# Adafruit_Feather_M0_RFMxx.net
KiCad netlist of a schematic drawn in EAGLE
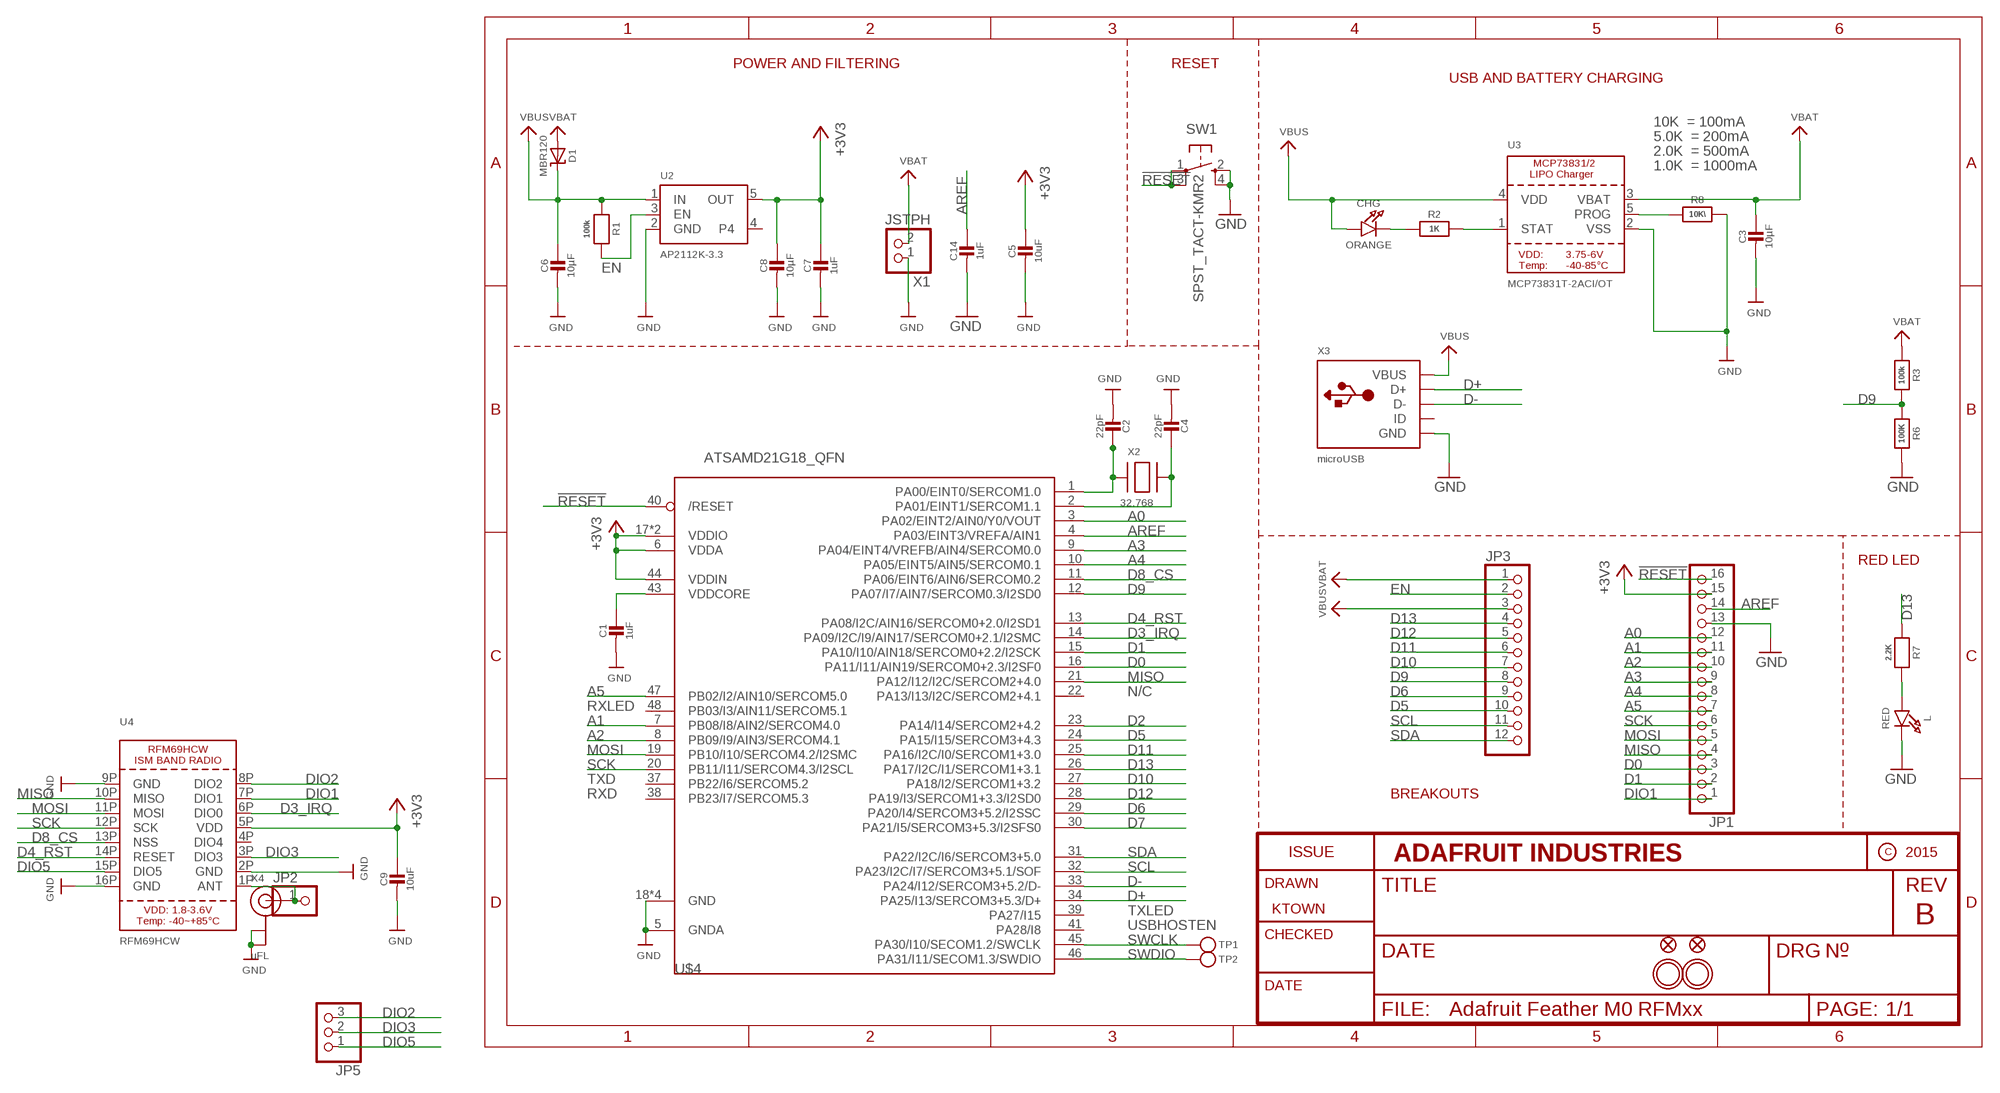
[diagram p0: schematic, sheet 1]

(export (version "E")
  (design (tool "Eeschema 10.0.6"))
  (components
    (comp (ref "C1")
      (value "1uF")
      (footprint "eagle-import:0603-NO")
      (libsource (lib "eagle-import") (part "CAP_CERAMIC0603_NO"))
    )
    (comp (ref "C2")
      (value "22pF")
      (footprint "eagle-import:0603-NO")
      (libsource (lib "eagle-import") (part "CAP_CERAMIC0603_NO"))
    )
    (comp (ref "C3")
      (value "10µF")
      (footprint "eagle-import:0805-NO")
      (libsource (lib "eagle-import") (part "CAP_CERAMIC0805-NOOUTLINE"))
    )
    (comp (ref "C4")
      (value "22pF")
      (footprint "eagle-import:0603-NO")
      (libsource (lib "eagle-import") (part "CAP_CERAMIC0603_NO"))
    )
    (comp (ref "C5")
      (value "10uF")
      (footprint "eagle-import:0805-NO")
      (libsource (lib "eagle-import") (part "CAP_CERAMIC0805-NOOUTLINE"))
    )
    (comp (ref "C6")
      (value "10µF")
      (footprint "eagle-import:0805-NO")
      (libsource (lib "eagle-import") (part "CAP_CERAMIC0805-NOOUTLINE"))
    )
    (comp (ref "C7")
      (value "1uF")
      (footprint "eagle-import:0603-NO")
      (libsource (lib "eagle-import") (part "CAP_CERAMIC0603_NO"))
    )
    (comp (ref "C8")
      (value "10µF")
      (footprint "eagle-import:0805-NO")
      (libsource (lib "eagle-import") (part "CAP_CERAMIC0805-NOOUTLINE"))
    )
    (comp (ref "C9")
      (value "10uF")
      (footprint "eagle-import:0805-NO")
      (libsource (lib "eagle-import") (part "CAP_CERAMIC0805-NOOUTLINE"))
    )
    (comp (ref "C14")
      (value "1uF")
      (footprint "eagle-import:0603-NO")
      (libsource (lib "eagle-import") (part "CAP_CERAMIC0603_NO"))
    )
    (comp (ref "CHG")
      (value "ORANGE")
      (footprint "eagle-import:CHIPLED_0805_NOOUTLINE")
      (libsource (lib "eagle-import") (part "LED0805_NOOUTLINE"))
    )
    (comp (ref "D1")
      (value "MBR120")
      (footprint "eagle-import:SOD-123")
      (libsource (lib "eagle-import") (part "DIODE-SCHOTTKYSOD-123"))
    )
    (comp (ref "JP1")
      (value "HEADER-1X16ROUND")
      (footprint "eagle-import:1X16_ROUND")
      (libsource (lib "eagle-import") (part "HEADER-1X16ROUND"))
    )
    (comp (ref "JP2")
      (value "HEADER-1X1ROUND")
      (footprint "eagle-import:1X01_ROUND")
      (libsource (lib "eagle-import") (part "HEADER-1X1ROUND"))
    )
    (comp (ref "JP3")
      (value "HEADER-1X12")
      (footprint "eagle-import:1X12_ROUND")
      (libsource (lib "eagle-import") (part "HEADER-1X12"))
    )
    (comp (ref "JP5")
      (value "HEADER-1X3ROUND")
      (footprint "eagle-import:1X03_ROUND")
      (libsource (lib "eagle-import") (part "HEADER-1X3ROUND"))
    )
    (comp (ref "L")
      (value "RED")
      (footprint "eagle-import:CHIPLED_0805_NOOUTLINE")
      (libsource (lib "eagle-import") (part "LED0805_NOOUTLINE"))
    )
    (comp (ref "R1")
      (value "100k")
      (footprint "eagle-import:0603-NO")
      (libsource (lib "eagle-import") (part "RESISTOR_0603_NOOUT"))
    )
    (comp (ref "R2")
      (value "1K")
      (footprint "eagle-import:0603-NO")
      (libsource (lib "eagle-import") (part "RESISTOR_0603_NOOUT"))
    )
    (comp (ref "R3")
      (value "100k")
      (footprint "eagle-import:0603-NO")
      (libsource (lib "eagle-import") (part "RESISTOR_0603_NOOUT"))
    )
    (comp (ref "R6")
      (value "100K")
      (footprint "eagle-import:0603-NO")
      (libsource (lib "eagle-import") (part "RESISTOR_0603_NOOUT"))
    )
    (comp (ref "R7")
      (value "2.2K")
      (footprint "eagle-import:0603-NO")
      (libsource (lib "eagle-import") (part "RESISTOR_0603_NOOUT"))
    )
    (comp (ref "R8")
      (value "10K\\")
      (footprint "eagle-import:0603-NO")
      (libsource (lib "eagle-import") (part "RESISTOR_0603_NOOUT"))
    )
    (comp (ref "SW1")
      (value "SPST_TACT-KMR2")
      (footprint "eagle-import:KMR2")
      (libsource (lib "eagle-import") (part "SPST_TACT-KMR2"))
    )
    (comp (ref "TP1")
      (value "TESTPOINTROUND1.5MM")
      (footprint "eagle-import:TESTPOINT_ROUND_1.5MM")
      (libsource (lib "eagle-import") (part "TESTPOINTROUND1.5MM"))
    )
    (comp (ref "TP2")
      (value "TESTPOINTROUND1.5MM")
      (footprint "eagle-import:TESTPOINT_ROUND_1.5MM")
      (libsource (lib "eagle-import") (part "TESTPOINTROUND1.5MM"))
    )
    (comp (ref "U$4")
      (value "ATSAMD21G18_QFN")
      (footprint "eagle-import:TQFN48_7MM")
      (libsource (lib "eagle-import") (part "ATSAMD21J_QFN"))
    )
    (comp (ref "U$31")
      (value "MOUNTINGHOLE2.5")
      (footprint "eagle-import:MOUNTINGHOLE_2.5_PLATED")
      (libsource (lib "eagle-import") (part "MOUNTINGHOLE2.5"))
    )
    (comp (ref "U$32")
      (value "MOUNTINGHOLE2.5")
      (footprint "eagle-import:MOUNTINGHOLE_2.5_PLATED")
      (libsource (lib "eagle-import") (part "MOUNTINGHOLE2.5"))
    )
    (comp (ref "U$34")
      (value "FIDUCIAL\"\"")
      (footprint "eagle-import:FIDUCIAL_1MM")
      (libsource (lib "eagle-import") (part "FIDUCIAL{dblquote}{dblquote}"))
    )
    (comp (ref "U$35")
      (value "FIDUCIAL\"\"")
      (footprint "eagle-import:FIDUCIAL_1MM")
      (libsource (lib "eagle-import") (part "FIDUCIAL{dblquote}{dblquote}"))
    )
    (comp (ref "U2")
      (value "AP2112K-3.3")
      (footprint "eagle-import:SOT23-5")
      (libsource (lib "eagle-import") (part "VREG_SOT23-5"))
    )
    (comp (ref "U3")
      (value "MCP73831T-2ACI/OT")
      (footprint "eagle-import:SOT23-5")
      (libsource (lib "eagle-import") (part "MCP73831/2"))
    )
    (comp (ref "U4")
      (value "RFM69HCW")
      (footprint "eagle-import:RFMHCW_SMT")
      (libsource (lib "eagle-import") (part "RFM69HCW_SMT"))
    )
    (comp (ref "X1")
      (value "JSTPH")
      (footprint "eagle-import:JSTPH2")
      (libsource (lib "eagle-import") (part "CON_JST_PH_2PIN"))
    )
    (comp (ref "X2")
      (value "32.768")
      (footprint "eagle-import:XTAL3215")
      (libsource (lib "eagle-import") (part "XTAL-3.2X1.5"))
    )
    (comp (ref "X3")
      (value "microUSB")
      (footprint "eagle-import:4UCONN_20329_V2")
      (libsource (lib "eagle-import") (part "USB_MICRO_20329_V2"))
    )
    (comp (ref "X4")
      (value "uFL")
      (footprint "eagle-import:U.FL")
      (libsource (lib "eagle-import") (part "ANTENNA_U.FL"))
    )
  )
  (nets
    (net (code "1") (name "+3V3") (class "Default")
      (node (ref "C5") (pin "1") (pinfunction "1_1") (pintype "passive"))
      (node (ref "C7") (pin "1") (pinfunction "1_1") (pintype "passive"))
      (node (ref "C8") (pin "1") (pinfunction "1_1") (pintype "passive"))
      (node (ref "C9") (pin "1") (pinfunction "1_1") (pintype "passive"))
      (node (ref "JP1") (pin "15") (pinfunction "15_15") (pintype "passive"))
      (node (ref "U$4") (pin "17") (pinfunction "VDDIO_17") (pintype "power_in"))
      (node (ref "U$4") (pin "36") (pinfunction "VDDIO_36") (pintype "power_in"))
      (node (ref "U$4") (pin "44") (pinfunction "VDDIN_44") (pintype "power_in"))
      (node (ref "U$4") (pin "6") (pinfunction "VDDA_6") (pintype "power_in"))
      (node (ref "U2") (pin "5") (pinfunction "OUT_5") (pintype "power_in"))
      (node (ref "U4") (pin "5P") (pinfunction "VDD_5P") (pintype "power_in"))
    )
    (net (code "2") (name "/A0") (class "Default")
      (node (ref "JP1") (pin "12") (pinfunction "12_12") (pintype "passive"))
      (node (ref "U$4") (pin "3") (pinfunction "PA02/EINT2/AIN0/Y0/VOUT_3") (pintype "bidirectional"))
    )
    (net (code "3") (name "/A1") (class "Default")
      (node (ref "JP1") (pin "11") (pinfunction "11_11") (pintype "passive"))
      (node (ref "U$4") (pin "7") (pinfunction "PB08/I8/AIN2/SERCOM4.0_7") (pintype "bidirectional"))
    )
    (net (code "4") (name "/A2") (class "Default")
      (node (ref "JP1") (pin "10") (pinfunction "10_10") (pintype "passive"))
      (node (ref "U$4") (pin "8") (pinfunction "PB09/I9/AIN3/SERCOM4.1_8") (pintype "bidirectional"))
    )
    (net (code "5") (name "/A3") (class "Default")
      (node (ref "JP1") (pin "9") (pinfunction "9_9") (pintype "passive"))
      (node (ref "U$4") (pin "9") (pinfunction "PA04/EINT4/VREFB/AIN4/SERCOM0.0_9") (pintype "bidirectional"))
    )
    (net (code "6") (name "/A4") (class "Default")
      (node (ref "JP1") (pin "8") (pinfunction "8_8") (pintype "passive"))
      (node (ref "U$4") (pin "10") (pinfunction "PA05/EINT5/AIN5/SERCOM0.1_10") (pintype "bidirectional"))
    )
    (net (code "7") (name "/A5") (class "Default")
      (node (ref "JP1") (pin "7") (pinfunction "7_7") (pintype "passive"))
      (node (ref "U$4") (pin "47") (pinfunction "PB02/I2/AIN10/SERCOM5.0_47") (pintype "bidirectional"))
    )
    (net (code "8") (name "/AREF") (class "Default")
      (node (ref "C14") (pin "1") (pinfunction "1_1") (pintype "passive"))
      (node (ref "JP1") (pin "14") (pinfunction "14_14") (pintype "passive"))
      (node (ref "U$4") (pin "4") (pinfunction "PA03/EINT3/VREFA/AIN1_4") (pintype "bidirectional"))
    )
    (net (code "9") (name "/D+") (class "Default")
      (node (ref "U$4") (pin "34") (pinfunction "PA25/I13/SERCOM3+5.3/D+_34") (pintype "bidirectional"))
      (node (ref "X3") (pin "D+") (pinfunction "D+_D+") (pintype "bidirectional"))
    )
    (net (code "10") (name "/D-") (class "Default")
      (node (ref "U$4") (pin "33") (pinfunction "PA24/I12/SERCOM3+5.2/D-_33") (pintype "bidirectional"))
      (node (ref "X3") (pin "D-") (pinfunction "D-_D-") (pintype "bidirectional"))
    )
    (net (code "11") (name "/D0") (class "Default")
      (node (ref "JP1") (pin "3") (pinfunction "3_3") (pintype "passive"))
      (node (ref "U$4") (pin "16") (pinfunction "PA11/I11/AIN19/SERCOM0+2.3/I2SF0_16") (pintype "bidirectional"))
    )
    (net (code "12") (name "/D1") (class "Default")
      (node (ref "JP1") (pin "2") (pinfunction "2_2") (pintype "passive"))
      (node (ref "U$4") (pin "15") (pinfunction "PA10/I10/AIN18/SERCOM0+2.2/I2SCK_15") (pintype "bidirectional"))
    )
    (net (code "13") (name "/D2") (class "Default")
      (node (ref "U$4") (pin "23") (pinfunction "PA14/I14/SERCOM2+4.2_23") (pintype "bidirectional"))
    )
    (net (code "14") (name "/D3_IRQ") (class "Default")
      (node (ref "U$4") (pin "14") (pinfunction "PA09/I2C/I9/AIN17/SERCOM0+2.1/I2SMC_14") (pintype "bidirectional"))
      (node (ref "U4") (pin "6P") (pinfunction "DIO0_6P") (pintype "bidirectional"))
    )
    (net (code "15") (name "/D4_RST") (class "Default")
      (node (ref "U$4") (pin "13") (pinfunction "PA08/I2C/AIN16/SERCOM0+2.0/I2SD1_13") (pintype "bidirectional"))
      (node (ref "U4") (pin "14P") (pinfunction "RESET_14P") (pintype "input"))
    )
    (net (code "16") (name "/D5") (class "Default")
      (node (ref "JP3") (pin "10") (pinfunction "10_10") (pintype "passive"))
      (node (ref "U$4") (pin "24") (pinfunction "PA15/I15/SERCOM3+4.3_24") (pintype "bidirectional"))
    )
    (net (code "17") (name "/D6") (class "Default")
      (node (ref "JP3") (pin "9") (pinfunction "9_9") (pintype "passive"))
      (node (ref "U$4") (pin "29") (pinfunction "PA20/I4/SERCOM3+5.2/I2SSC_29") (pintype "bidirectional"))
    )
    (net (code "18") (name "/D7") (class "Default")
      (node (ref "U$4") (pin "30") (pinfunction "PA21/I5/SERCOM3+5.3/I2SFS0_30") (pintype "bidirectional"))
    )
    (net (code "19") (name "/D8_CS") (class "Default")
      (node (ref "U$4") (pin "11") (pinfunction "PA06/EINT6/AIN6/SERCOM0.2_11") (pintype "bidirectional"))
      (node (ref "U4") (pin "13P") (pinfunction "NSS_13P") (pintype "input"))
    )
    (net (code "20") (name "/D9") (class "Default")
      (node (ref "JP3") (pin "8") (pinfunction "8_8") (pintype "passive"))
      (node (ref "R3") (pin "2") (pinfunction "2_2") (pintype "passive"))
      (node (ref "R6") (pin "1") (pinfunction "1_1") (pintype "passive"))
      (node (ref "U$4") (pin "12") (pinfunction "PA07/I7/AIN7/SERCOM0.3/I2SD0_12") (pintype "bidirectional"))
    )
    (net (code "21") (name "/D10") (class "Default")
      (node (ref "JP3") (pin "7") (pinfunction "7_7") (pintype "passive"))
      (node (ref "U$4") (pin "27") (pinfunction "PA18/I2/SERCOM1+3.2_27") (pintype "bidirectional"))
    )
    (net (code "22") (name "/D11") (class "Default")
      (node (ref "JP3") (pin "6") (pinfunction "6_6") (pintype "passive"))
      (node (ref "U$4") (pin "25") (pinfunction "PA16/I2C/I0/SERCOM1+3.0_25") (pintype "bidirectional"))
    )
    (net (code "23") (name "/D12") (class "Default")
      (node (ref "JP3") (pin "5") (pinfunction "5_5") (pintype "passive"))
      (node (ref "U$4") (pin "28") (pinfunction "PA19/I3/SERCOM1+3.3/I2SD0_28") (pintype "bidirectional"))
    )
    (net (code "24") (name "/D13") (class "Default")
      (node (ref "JP3") (pin "4") (pinfunction "4_4") (pintype "passive"))
      (node (ref "R7") (pin "1") (pinfunction "1_1") (pintype "passive"))
      (node (ref "U$4") (pin "26") (pinfunction "PA17/I2C/I1/SERCOM1+3.1_26") (pintype "bidirectional"))
    )
    (net (code "25") (name "/DIO1") (class "Default")
      (node (ref "JP1") (pin "1") (pinfunction "1_1") (pintype "passive"))
      (node (ref "U4") (pin "7P") (pinfunction "DIO1_7P") (pintype "bidirectional"))
    )
    (net (code "26") (name "/DIO2") (class "Default")
      (node (ref "JP5") (pin "3") (pinfunction "3_3") (pintype "passive"))
      (node (ref "U4") (pin "8P") (pinfunction "DIO2_8P") (pintype "bidirectional"))
    )
    (net (code "27") (name "/DIO3") (class "Default")
      (node (ref "JP5") (pin "2") (pinfunction "2_2") (pintype "passive"))
      (node (ref "U4") (pin "3P") (pinfunction "DIO3_3P") (pintype "bidirectional"))
    )
    (net (code "28") (name "/DIO5") (class "Default")
      (node (ref "JP5") (pin "1") (pinfunction "1_1") (pintype "passive"))
      (node (ref "U4") (pin "15P") (pinfunction "DIO5_15P") (pintype "bidirectional"))
    )
    (net (code "29") (name "/EN") (class "Default")
      (node (ref "JP3") (pin "2") (pinfunction "2_2") (pintype "passive"))
      (node (ref "R1") (pin "2") (pinfunction "2_2") (pintype "passive"))
      (node (ref "U2") (pin "3") (pinfunction "EN_3") (pintype "input"))
    )
    (net (code "30") (name "/MISO") (class "Default")
      (node (ref "JP1") (pin "4") (pinfunction "4_4") (pintype "passive"))
      (node (ref "U$4") (pin "21") (pinfunction "PA12/I12/I2C/SERCOM2+4.0_21") (pintype "bidirectional"))
      (node (ref "U4") (pin "10P") (pinfunction "MISO_10P") (pintype "output"))
    )
    (net (code "31") (name "/MOSI") (class "Default")
      (node (ref "JP1") (pin "5") (pinfunction "5_5") (pintype "passive"))
      (node (ref "U$4") (pin "19") (pinfunction "PB10/I10/SERCOM4.2/I2SMC_19") (pintype "bidirectional"))
      (node (ref "U4") (pin "11P") (pinfunction "MOSI_11P") (pintype "input"))
    )
    (net (code "32") (name "/SCK") (class "Default")
      (node (ref "JP1") (pin "6") (pinfunction "6_6") (pintype "passive"))
      (node (ref "U$4") (pin "20") (pinfunction "PB11/I11/SERCOM4.3/I2SCL_20") (pintype "bidirectional"))
      (node (ref "U4") (pin "12P") (pinfunction "SCK_12P") (pintype "input"))
    )
    (net (code "33") (name "/SCL") (class "Default")
      (node (ref "JP3") (pin "11") (pinfunction "11_11") (pintype "passive"))
      (node (ref "U$4") (pin "32") (pinfunction "PA23/I2C/I7/SERCOM3+5.1/SOF_32") (pintype "bidirectional"))
    )
    (net (code "34") (name "/SDA") (class "Default")
      (node (ref "JP3") (pin "12") (pinfunction "12_12") (pintype "passive"))
      (node (ref "U$4") (pin "31") (pinfunction "PA22/I2C/I6/SERCOM3+5.0_31") (pintype "bidirectional"))
    )
    (net (code "35") (name "/SWCLK") (class "Default")
      (node (ref "TP1") (pin "P$1") (pinfunction "P$1_P$1") (pintype "bidirectional"))
      (node (ref "U$4") (pin "45") (pinfunction "PA30/I10/SECOM1.2/SWCLK_45") (pintype "bidirectional"))
    )
    (net (code "36") (name "/SWDIO") (class "Default")
      (node (ref "TP2") (pin "P$1") (pinfunction "P$1_P$1") (pintype "bidirectional"))
      (node (ref "U$4") (pin "46") (pinfunction "PA31/I11/SECOM1.3/SWDIO_46") (pintype "bidirectional"))
    )
    (net (code "37") (name "/~{RESET}") (class "Default")
      (node (ref "JP1") (pin "16") (pinfunction "16_16") (pintype "passive"))
      (node (ref "SW1") (pin "1") (pinfunction "P_1") (pintype "passive"))
      (node (ref "SW1") (pin "3") (pinfunction "P1_3") (pintype "passive"))
      (node (ref "U$4") (pin "40") (pinfunction "/RESET_40") (pintype "bidirectional"))
    )
    (net (code "38") (name "GND") (class "Default")
      (node (ref "C1") (pin "2") (pinfunction "2_2") (pintype "passive"))
      (node (ref "C14") (pin "2") (pinfunction "2_2") (pintype "passive"))
      (node (ref "C2") (pin "2") (pinfunction "2_2") (pintype "passive"))
      (node (ref "C3") (pin "2") (pinfunction "2_2") (pintype "passive"))
      (node (ref "C4") (pin "2") (pinfunction "2_2") (pintype "passive"))
      (node (ref "C5") (pin "2") (pinfunction "2_2") (pintype "passive"))
      (node (ref "C6") (pin "2") (pinfunction "2_2") (pintype "passive"))
      (node (ref "C7") (pin "2") (pinfunction "2_2") (pintype "passive"))
      (node (ref "C8") (pin "2") (pinfunction "2_2") (pintype "passive"))
      (node (ref "C9") (pin "2") (pinfunction "2_2") (pintype "passive"))
      (node (ref "JP1") (pin "13") (pinfunction "13_13") (pintype "passive"))
      (node (ref "L") (pin "C") (pinfunction "C_C") (pintype "passive"))
      (node (ref "R6") (pin "2") (pinfunction "2_2") (pintype "passive"))
      (node (ref "R8") (pin "2") (pinfunction "2_2") (pintype "passive"))
      (node (ref "SW1") (pin "2") (pinfunction "S_2") (pintype "passive"))
      (node (ref "SW1") (pin "4") (pinfunction "S1_4") (pintype "passive"))
      (node (ref "U$4") (pin "18") (pinfunction "GND_18") (pintype "power_in"))
      (node (ref "U$4") (pin "35") (pinfunction "GND_35") (pintype "power_in"))
      (node (ref "U$4") (pin "42") (pinfunction "GND_42") (pintype "power_in"))
      (node (ref "U$4") (pin "5") (pinfunction "GNDA_5") (pintype "power_in"))
      (node (ref "U$4") (pin "THERMAL") (pinfunction "GND_THERMAL") (pintype "power_in"))
      (node (ref "U2") (pin "2") (pinfunction "GND_2") (pintype "power_in"))
      (node (ref "U3") (pin "2") (pinfunction "VSS_2") (pintype "power_in"))
      (node (ref "U4") (pin "16P") (pinfunction "GND_16P") (pintype "power_in"))
      (node (ref "U4") (pin "2P") (pinfunction "GND_2P") (pintype "power_in"))
      (node (ref "U4") (pin "9P") (pinfunction "GND_9P") (pintype "power_in"))
      (node (ref "X1") (pin "1") (pinfunction "1_1") (pintype "passive"))
      (node (ref "X3") (pin "BASE@1") (pinfunction "GND_BASE@1") (pintype "power_in"))
      (node (ref "X3") (pin "BASE@2") (pinfunction "GND_BASE@2") (pintype "power_in"))
      (node (ref "X3") (pin "GND") (pinfunction "GND_GND") (pintype "power_in"))
      (node (ref "X3") (pin "SPRT@1") (pinfunction "GND_SPRT@1") (pintype "power_in"))
      (node (ref "X3") (pin "SPRT@2") (pinfunction "GND_SPRT@2") (pintype "power_in"))
      (node (ref "X3") (pin "SPRT@3") (pinfunction "GND_SPRT@3") (pintype "power_in"))
      (node (ref "X3") (pin "SPRT@4") (pinfunction "GND_SPRT@4") (pintype "power_in"))
      (node (ref "X4") (pin "1") (pinfunction "GND_1") (pintype "passive"))
      (node (ref "X4") (pin "2") (pinfunction "GND_2") (pintype "passive"))
    )
    (net (code "39") (name "Net-(CHG-PadC)") (class "Default")
      (node (ref "CHG") (pin "C") (pinfunction "C_C") (pintype "passive"))
      (node (ref "R2") (pin "1") (pinfunction "1_1") (pintype "passive"))
    )
    (net (code "40") (name "Net-(L-PadA)") (class "Default")
      (node (ref "L") (pin "A") (pinfunction "A_A") (pintype "passive"))
      (node (ref "R7") (pin "2") (pinfunction "2_2") (pintype "passive"))
    )
    (net (code "41") (name "Net-(U$4-PA00{slash}EINT0{slash}SERCOM1.0)") (class "Default")
      (node (ref "C2") (pin "1") (pinfunction "1_1") (pintype "passive"))
      (node (ref "U$4") (pin "1") (pinfunction "PA00/EINT0/SERCOM1.0_1") (pintype "bidirectional"))
      (node (ref "X2") (pin "P$1") (pinfunction "P$1_P$1") (pintype "bidirectional"))
    )
    (net (code "42") (name "Net-(U$4-PA01{slash}EINT1{slash}SERCOM1.1)") (class "Default")
      (node (ref "C4") (pin "1") (pinfunction "1_1") (pintype "passive"))
      (node (ref "U$4") (pin "2") (pinfunction "PA01/EINT1/SERCOM1.1_2") (pintype "bidirectional"))
      (node (ref "X2") (pin "P$2") (pinfunction "P$2_P$2") (pintype "bidirectional"))
    )
    (net (code "43") (name "Net-(U$4-VDDCORE)") (class "Default")
      (node (ref "C1") (pin "1") (pinfunction "1_1") (pintype "passive"))
      (node (ref "U$4") (pin "43") (pinfunction "VDDCORE_43") (pintype "power_in"))
    )
    (net (code "44") (name "Net-(U3-PROG)") (class "Default")
      (node (ref "R8") (pin "1") (pinfunction "1_1") (pintype "passive"))
      (node (ref "U3") (pin "5") (pinfunction "PROG_5") (pintype "input"))
    )
    (net (code "45") (name "Net-(U3-STAT)") (class "Default")
      (node (ref "R2") (pin "2") (pinfunction "2_2") (pintype "passive"))
      (node (ref "U3") (pin "1") (pinfunction "STAT_1") (pintype "output"))
    )
    (net (code "46") (name "Net-(U4-ANT)") (class "Default")
      (node (ref "JP2") (pin "1") (pinfunction "1_1") (pintype "passive"))
      (node (ref "U4") (pin "1P") (pinfunction "ANT_1P") (pintype "bidirectional"))
      (node (ref "X4") (pin "3") (pinfunction "SIGNAL_3") (pintype "passive"))
    )
    (net (code "47") (name "VBAT") (class "Default")
      (node (ref "C3") (pin "1") (pinfunction "1_1") (pintype "passive"))
      (node (ref "D1") (pin "A") (pinfunction "A_A") (pintype "passive"))
      (node (ref "JP3") (pin "1") (pinfunction "1_1") (pintype "passive"))
      (node (ref "R3") (pin "1") (pinfunction "1_1") (pintype "passive"))
      (node (ref "U3") (pin "3") (pinfunction "VBAT_3") (pintype "power_in"))
      (node (ref "X1") (pin "2") (pinfunction "2_2") (pintype "passive"))
    )
    (net (code "48") (name "VBUS") (class "Default")
      (node (ref "C6") (pin "1") (pinfunction "1_1") (pintype "passive"))
      (node (ref "CHG") (pin "A") (pinfunction "A_A") (pintype "passive"))
      (node (ref "D1") (pin "C") (pinfunction "C_C") (pintype "passive"))
      (node (ref "JP3") (pin "3") (pinfunction "3_3") (pintype "passive"))
      (node (ref "R1") (pin "1") (pinfunction "1_1") (pintype "passive"))
      (node (ref "U2") (pin "1") (pinfunction "IN_1") (pintype "power_in"))
      (node (ref "U3") (pin "4") (pinfunction "VDD_4") (pintype "power_in"))
      (node (ref "X3") (pin "VBUS") (pinfunction "VBUS_VBUS") (pintype "power_in"))
    )
    (net (code "49") (name "unconnected-(U$4-PA13{slash}I13{slash}I2C{slash}SERCOM2+4.1-Pad22)") (class "Default")
      (node (ref "U$4") (pin "22") (pinfunction "PA13/I13/I2C/SERCOM2+4.1_22") (pintype "bidirectional"))
    )
    (net (code "50") (name "unconnected-(U$4-PA27{slash}I15-Pad39)") (class "Default")
      (node (ref "U$4") (pin "39") (pinfunction "PA27/I15_39") (pintype "bidirectional"))
    )
    (net (code "51") (name "unconnected-(U$4-PA28{slash}I8-Pad41)") (class "Default")
      (node (ref "U$4") (pin "41") (pinfunction "PA28/I8_41") (pintype "bidirectional"))
    )
    (net (code "52") (name "unconnected-(U$4-PB03{slash}I3{slash}AIN11{slash}SERCOM5.1-Pad48)") (class "Default")
      (node (ref "U$4") (pin "48") (pinfunction "PB03/I3/AIN11/SERCOM5.1_48") (pintype "bidirectional"))
    )
    (net (code "53") (name "unconnected-(U$4-PB22{slash}I6{slash}SERCOM5.2-Pad37)") (class "Default")
      (node (ref "U$4") (pin "37") (pinfunction "PB22/I6/SERCOM5.2_37") (pintype "bidirectional"))
    )
    (net (code "54") (name "unconnected-(U$4-PB23{slash}I7{slash}SERCOM5.3-Pad38)") (class "Default")
      (node (ref "U$4") (pin "38") (pinfunction "PB23/I7/SERCOM5.3_38") (pintype "bidirectional"))
    )
    (net (code "55") (name "unconnected-(U2-P4-Pad4)") (class "Default")
      (node (ref "U2") (pin "4") (pinfunction "P4_4") (pintype "bidirectional"))
    )
    (net (code "56") (name "unconnected-(U4-DIO4-Pad4P)") (class "Default")
      (node (ref "U4") (pin "4P") (pinfunction "DIO4_4P") (pintype "bidirectional"))
    )
    (net (code "57") (name "unconnected-(X3-PadID)") (class "Default")
      (node (ref "X3") (pin "ID") (pinfunction "ID_ID") (pintype "bidirectional"))
    )
  )
)
